# ME433-2021.net
KiCad netlist of a schematic drawn in EAGLE
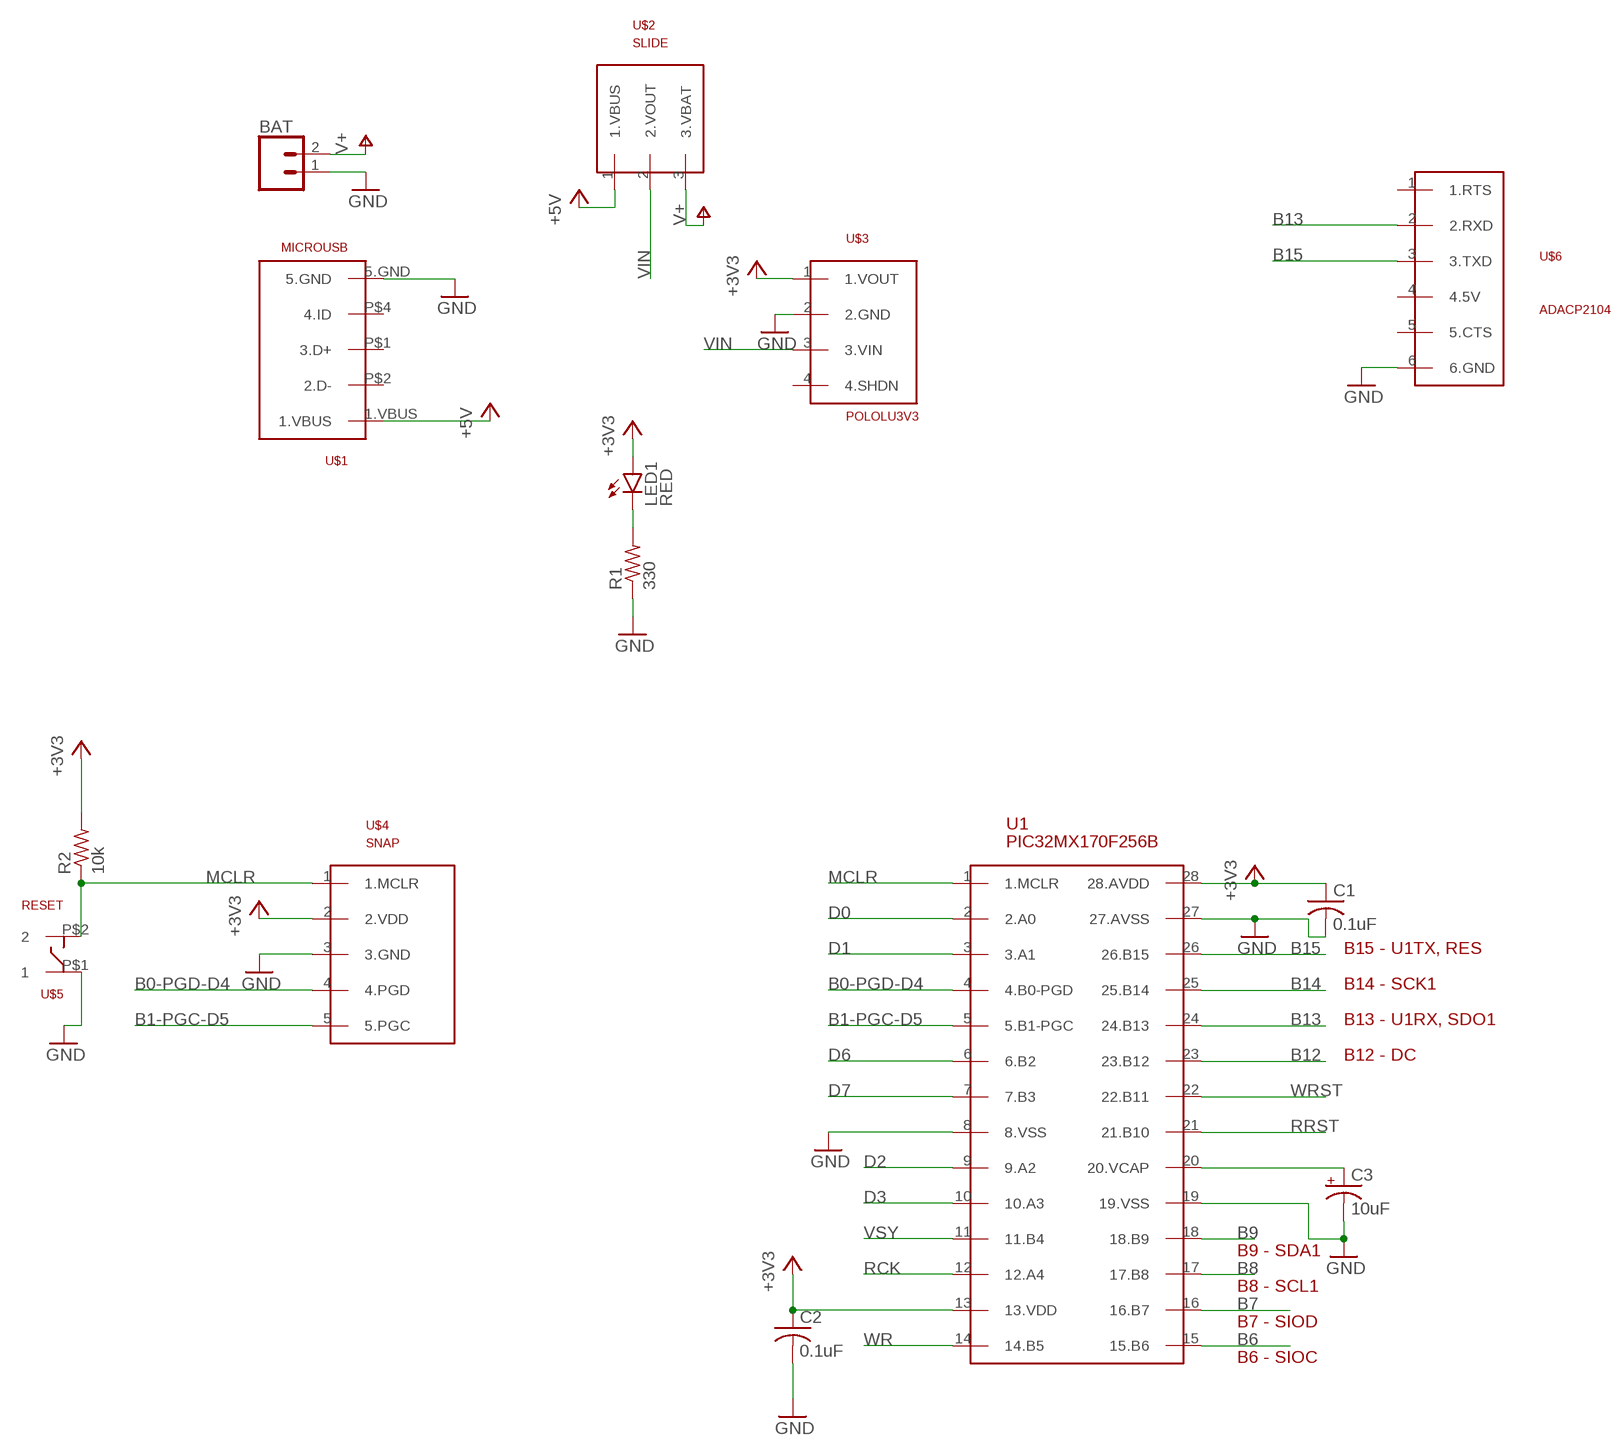
[diagram p0: schematic, sheet 1, part 1 of 2]
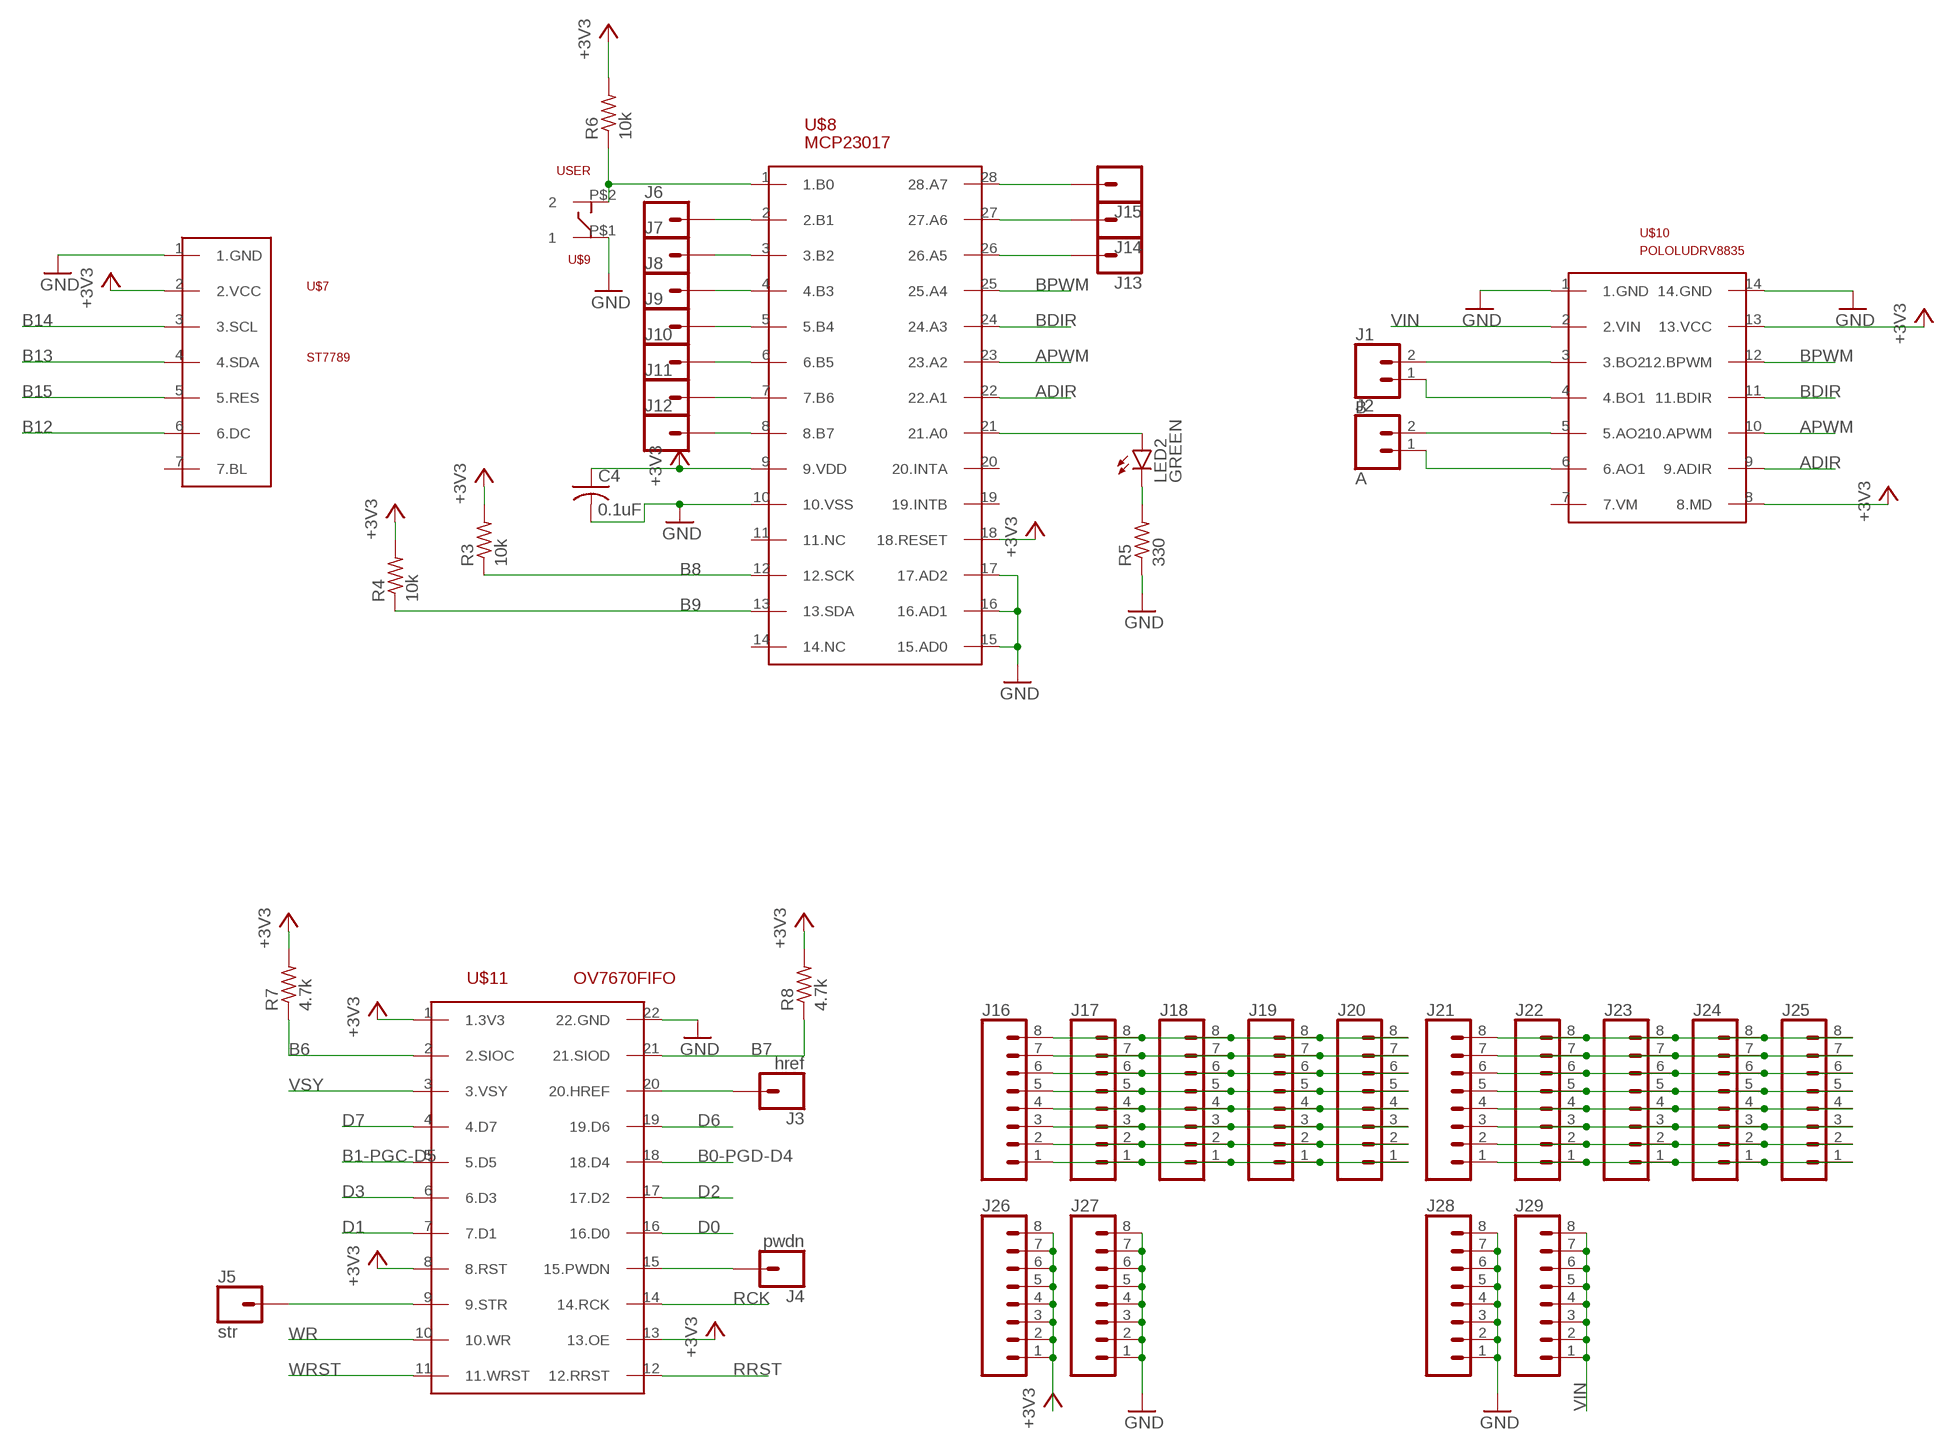
[diagram p1: schematic, sheet 1, part 2 of 2]

(export (version "E")
  (design (tool "Eeschema 10.0.6"))
  (components
    (comp (ref "BAT")
      (value "CONN_02")
      (footprint "eagle-import:1X02")
      (libsource (lib "eagle-import") (part "CONN_02"))
    )
    (comp (ref "C1")
      (value "0.1uF")
      (footprint "eagle-import:C025-030X050")
      (libsource (lib "eagle-import") (part "C-US025-030X050"))
    )
    (comp (ref "C2")
      (value "0.1uF")
      (footprint "eagle-import:C025-030X050")
      (libsource (lib "eagle-import") (part "C-US025-030X050"))
    )
    (comp (ref "C3")
      (value "10uF")
      (footprint "eagle-import:B45181B")
      (libsource (lib "eagle-import") (part "CPOL-USB45181B"))
    )
    (comp (ref "C4")
      (value "0.1uF")
      (footprint "eagle-import:C025-030X050")
      (libsource (lib "eagle-import") (part "C-US025-030X050"))
    )
    (comp (ref "J1")
      (value "B")
      (footprint "eagle-import:1X02")
      (libsource (lib "eagle-import") (part "CONN_02"))
    )
    (comp (ref "J2")
      (value "A")
      (footprint "eagle-import:1X02")
      (libsource (lib "eagle-import") (part "CONN_02"))
    )
    (comp (ref "J3")
      (value "href")
      (footprint "eagle-import:1X01")
      (libsource (lib "eagle-import") (part "CONN_01"))
    )
    (comp (ref "J4")
      (value "pwdn")
      (footprint "eagle-import:1X01")
      (libsource (lib "eagle-import") (part "CONN_01"))
    )
    (comp (ref "J5")
      (value "str")
      (footprint "eagle-import:1X01")
      (libsource (lib "eagle-import") (part "CONN_01"))
    )
    (comp (ref "J6")
      (value "CONN_01")
      (footprint "eagle-import:1X01")
      (libsource (lib "eagle-import") (part "CONN_01"))
    )
    (comp (ref "J7")
      (value "CONN_01")
      (footprint "eagle-import:1X01")
      (libsource (lib "eagle-import") (part "CONN_01"))
    )
    (comp (ref "J8")
      (value "CONN_01")
      (footprint "eagle-import:1X01")
      (libsource (lib "eagle-import") (part "CONN_01"))
    )
    (comp (ref "J9")
      (value "CONN_01")
      (footprint "eagle-import:1X01")
      (libsource (lib "eagle-import") (part "CONN_01"))
    )
    (comp (ref "J10")
      (value "CONN_01")
      (footprint "eagle-import:1X01")
      (libsource (lib "eagle-import") (part "CONN_01"))
    )
    (comp (ref "J11")
      (value "CONN_01")
      (footprint "eagle-import:1X01")
      (libsource (lib "eagle-import") (part "CONN_01"))
    )
    (comp (ref "J12")
      (value "CONN_01")
      (footprint "eagle-import:1X01")
      (libsource (lib "eagle-import") (part "CONN_01"))
    )
    (comp (ref "J13")
      (value "CONN_01")
      (footprint "eagle-import:1X01")
      (libsource (lib "eagle-import") (part "CONN_01"))
    )
    (comp (ref "J14")
      (value "CONN_01")
      (footprint "eagle-import:1X01")
      (libsource (lib "eagle-import") (part "CONN_01"))
    )
    (comp (ref "J15")
      (value "CONN_01")
      (footprint "eagle-import:1X01")
      (libsource (lib "eagle-import") (part "CONN_01"))
    )
    (comp (ref "J16")
      (value "CONN_08\"")
      (footprint "eagle-import:1X08")
      (libsource (lib "eagle-import") (part "CONN_08{dblquote}"))
    )
    (comp (ref "J17")
      (value "CONN_08\"")
      (footprint "eagle-import:1X08")
      (libsource (lib "eagle-import") (part "CONN_08{dblquote}"))
    )
    (comp (ref "J18")
      (value "CONN_08\"")
      (footprint "eagle-import:1X08")
      (libsource (lib "eagle-import") (part "CONN_08{dblquote}"))
    )
    (comp (ref "J19")
      (value "CONN_08\"")
      (footprint "eagle-import:1X08")
      (libsource (lib "eagle-import") (part "CONN_08{dblquote}"))
    )
    (comp (ref "J20")
      (value "CONN_08\"")
      (footprint "eagle-import:1X08")
      (libsource (lib "eagle-import") (part "CONN_08{dblquote}"))
    )
    (comp (ref "J21")
      (value "CONN_08\"")
      (footprint "eagle-import:1X08")
      (libsource (lib "eagle-import") (part "CONN_08{dblquote}"))
    )
    (comp (ref "J22")
      (value "CONN_08\"")
      (footprint "eagle-import:1X08")
      (libsource (lib "eagle-import") (part "CONN_08{dblquote}"))
    )
    (comp (ref "J23")
      (value "CONN_08\"")
      (footprint "eagle-import:1X08")
      (libsource (lib "eagle-import") (part "CONN_08{dblquote}"))
    )
    (comp (ref "J24")
      (value "CONN_08\"")
      (footprint "eagle-import:1X08")
      (libsource (lib "eagle-import") (part "CONN_08{dblquote}"))
    )
    (comp (ref "J25")
      (value "CONN_08\"")
      (footprint "eagle-import:1X08")
      (libsource (lib "eagle-import") (part "CONN_08{dblquote}"))
    )
    (comp (ref "J26")
      (value "CONN_08\"")
      (footprint "eagle-import:1X08")
      (libsource (lib "eagle-import") (part "CONN_08{dblquote}"))
    )
    (comp (ref "J27")
      (value "CONN_08\"")
      (footprint "eagle-import:1X08")
      (libsource (lib "eagle-import") (part "CONN_08{dblquote}"))
    )
    (comp (ref "J28")
      (value "CONN_08\"")
      (footprint "eagle-import:1X08")
      (libsource (lib "eagle-import") (part "CONN_08{dblquote}"))
    )
    (comp (ref "J29")
      (value "CONN_08\"")
      (footprint "eagle-import:1X08")
      (libsource (lib "eagle-import") (part "CONN_08{dblquote}"))
    )
    (comp (ref "LED1")
      (value "RED")
      (footprint "eagle-import:LED3MM")
      (libsource (lib "eagle-import") (part "LED3MM"))
    )
    (comp (ref "LED2")
      (value "GREEN")
      (footprint "eagle-import:LED3MM")
      (libsource (lib "eagle-import") (part "LED3MM"))
    )
    (comp (ref "R1")
      (value "330")
      (footprint "eagle-import:0207_10")
      (libsource (lib "eagle-import") (part "R-US_0207/10"))
    )
    (comp (ref "R2")
      (value "10k")
      (footprint "eagle-import:0207_10")
      (libsource (lib "eagle-import") (part "R-US_0207/10"))
    )
    (comp (ref "R3")
      (value "10k")
      (footprint "eagle-import:0207_10")
      (libsource (lib "eagle-import") (part "R-US_0207/10"))
    )
    (comp (ref "R4")
      (value "10k")
      (footprint "eagle-import:0207_10")
      (libsource (lib "eagle-import") (part "R-US_0207/10"))
    )
    (comp (ref "R5")
      (value "330")
      (footprint "eagle-import:0207_10")
      (libsource (lib "eagle-import") (part "R-US_0207/10"))
    )
    (comp (ref "R6")
      (value "10k")
      (footprint "eagle-import:0207_10")
      (libsource (lib "eagle-import") (part "R-US_0207/10"))
    )
    (comp (ref "R7")
      (value "4.7k")
      (footprint "eagle-import:0207_10")
      (libsource (lib "eagle-import") (part "R-US_0207/10"))
    )
    (comp (ref "R8")
      (value "4.7k")
      (footprint "eagle-import:0207_10")
      (libsource (lib "eagle-import") (part "R-US_0207/10"))
    )
    (comp (ref "U$1")
      (value "MICROUSB")
      (footprint "eagle-import:MICROUSB")
      (libsource (lib "eagle-import") (part "MICROUSB"))
    )
    (comp (ref "U$2")
      (value "SLIDE")
      (footprint "eagle-import:SLIDE")
      (libsource (lib "eagle-import") (part "SLIDE"))
    )
    (comp (ref "U$3")
      (value "POLOLU3V3")
      (footprint "eagle-import:POLOLU3V3")
      (libsource (lib "eagle-import") (part "POLOLU3V3"))
    )
    (comp (ref "U$4")
      (value "SNAP")
      (footprint "eagle-import:SNAP")
      (libsource (lib "eagle-import") (part "SNAP"))
    )
    (comp (ref "U$5")
      (value "RESET")
      (footprint "eagle-import:PUSH")
      (libsource (lib "eagle-import") (part "PUSH"))
    )
    (comp (ref "U$6")
      (value "ADACP2104")
      (footprint "eagle-import:ADACP2104")
      (libsource (lib "eagle-import") (part "ADACP2104"))
    )
    (comp (ref "U$7")
      (value "ST7789")
      (footprint "eagle-import:ST7789")
      (libsource (lib "eagle-import") (part "ST7789"))
    )
    (comp (ref "U$8")
      (value "MCP23017")
      (footprint "eagle-import:DIL28-3")
      (libsource (lib "eagle-import") (part "MCP23017"))
    )
    (comp (ref "U$9")
      (value "USER")
      (footprint "eagle-import:PUSH")
      (libsource (lib "eagle-import") (part "PUSH"))
    )
    (comp (ref "U$10")
      (value "POLOLUDRV8835")
      (footprint "eagle-import:POLOLUDRV8835")
      (libsource (lib "eagle-import") (part "POLOLUDRV8835"))
    )
    (comp (ref "U$11")
      (value "OV7670FIFO")
      (footprint "eagle-import:OV7670FIFO")
      (libsource (lib "eagle-import") (part "OV7670FIFO"))
    )
    (comp (ref "U1")
      (value "PIC32MX170F256B")
      (footprint "eagle-import:DIL28-3")
      (libsource (lib "eagle-import") (part "PIC32MX170F256B"))
    )
  )
  (nets
    (net (code "1") (name "+3V3") (class "Default")
      (node (ref "C1") (pin "1") (pinfunction "1_1") (pintype "passive"))
      (node (ref "C2") (pin "1") (pinfunction "1_1") (pintype "passive"))
      (node (ref "C4") (pin "1") (pinfunction "1_1") (pintype "passive"))
      (node (ref "J26") (pin "1") (pinfunction "1_1") (pintype "passive"))
      (node (ref "J26") (pin "2") (pinfunction "2_2") (pintype "passive"))
      (node (ref "J26") (pin "3") (pinfunction "3_3") (pintype "passive"))
      (node (ref "J26") (pin "4") (pinfunction "4_4") (pintype "passive"))
      (node (ref "J26") (pin "5") (pinfunction "5_5") (pintype "passive"))
      (node (ref "J26") (pin "6") (pinfunction "6_6") (pintype "passive"))
      (node (ref "J26") (pin "7") (pinfunction "7_7") (pintype "passive"))
      (node (ref "J26") (pin "8") (pinfunction "8_8") (pintype "passive"))
      (node (ref "LED1") (pin "A") (pinfunction "A_A") (pintype "passive"))
      (node (ref "R2") (pin "2") (pinfunction "2_2") (pintype "passive"))
      (node (ref "R3") (pin "2") (pinfunction "2_2") (pintype "passive"))
      (node (ref "R4") (pin "2") (pinfunction "2_2") (pintype "passive"))
      (node (ref "R6") (pin "2") (pinfunction "2_2") (pintype "passive"))
      (node (ref "R7") (pin "2") (pinfunction "2_2") (pintype "passive"))
      (node (ref "R8") (pin "2") (pinfunction "2_2") (pintype "passive"))
      (node (ref "U$10") (pin "13") (pinfunction "13.VCC_13") (pintype "bidirectional"))
      (node (ref "U$10") (pin "8") (pinfunction "8.MD_8") (pintype "bidirectional"))
      (node (ref "U$11") (pin "1") (pinfunction "1.3V3_1") (pintype "bidirectional"))
      (node (ref "U$11") (pin "13") (pinfunction "13.OE_13") (pintype "bidirectional"))
      (node (ref "U$11") (pin "8") (pinfunction "8.RST_8") (pintype "bidirectional"))
      (node (ref "U$3") (pin "1") (pinfunction "1.VOUT_1") (pintype "bidirectional"))
      (node (ref "U$4") (pin "2") (pinfunction "2.VDD_2") (pintype "bidirectional"))
      (node (ref "U$7") (pin "2") (pinfunction "2.VCC_2") (pintype "bidirectional"))
      (node (ref "U$8") (pin "18") (pinfunction "18.RESET_18") (pintype "bidirectional"))
      (node (ref "U$8") (pin "9") (pinfunction "9.VDD_9") (pintype "bidirectional"))
      (node (ref "U1") (pin "13") (pinfunction "13.VDD_13") (pintype "bidirectional"))
      (node (ref "U1") (pin "28") (pinfunction "28.AVDD_28") (pintype "bidirectional"))
    )
    (net (code "2") (name "+5V") (class "Default")
      (node (ref "U$1") (pin "1.VBUS") (pinfunction "1.VBUS_1.VBUS") (pintype "bidirectional"))
      (node (ref "U$2") (pin "1") (pinfunction "1.VBUS_1") (pintype "bidirectional"))
    )
    (net (code "3") (name "/ADIR") (class "Default")
      (node (ref "U$10") (pin "9") (pinfunction "9.ADIR_9") (pintype "bidirectional"))
      (node (ref "U$8") (pin "22") (pinfunction "22.A1_22") (pintype "bidirectional"))
    )
    (net (code "4") (name "/APWM") (class "Default")
      (node (ref "U$10") (pin "10") (pinfunction "10.APWM_10") (pintype "bidirectional"))
      (node (ref "U$8") (pin "23") (pinfunction "23.A2_23") (pintype "bidirectional"))
    )
    (net (code "5") (name "/B0-PGD-D4") (class "Default")
      (node (ref "U$11") (pin "18") (pinfunction "18.D4_18") (pintype "bidirectional"))
      (node (ref "U$4") (pin "4") (pinfunction "4.PGD_4") (pintype "bidirectional"))
      (node (ref "U1") (pin "4") (pinfunction "4.B0-PGD_4") (pintype "bidirectional"))
    )
    (net (code "6") (name "/B1-PGC-D5") (class "Default")
      (node (ref "U$11") (pin "5") (pinfunction "5.D5_5") (pintype "bidirectional"))
      (node (ref "U$4") (pin "5") (pinfunction "5.PGC_5") (pintype "bidirectional"))
      (node (ref "U1") (pin "5") (pinfunction "5.B1-PGC_5") (pintype "bidirectional"))
    )
    (net (code "7") (name "/B6") (class "Default")
      (node (ref "R7") (pin "1") (pinfunction "1_1") (pintype "passive"))
      (node (ref "U$11") (pin "2") (pinfunction "2.SIOC_2") (pintype "bidirectional"))
      (node (ref "U1") (pin "15") (pinfunction "15.B6_15") (pintype "bidirectional"))
    )
    (net (code "8") (name "/B7") (class "Default")
      (node (ref "R8") (pin "1") (pinfunction "1_1") (pintype "passive"))
      (node (ref "U$11") (pin "21") (pinfunction "21.SIOD_21") (pintype "bidirectional"))
      (node (ref "U1") (pin "16") (pinfunction "16.B7_16") (pintype "bidirectional"))
    )
    (net (code "9") (name "/B8") (class "Default")
      (node (ref "R3") (pin "1") (pinfunction "1_1") (pintype "passive"))
      (node (ref "U$8") (pin "12") (pinfunction "12.SCK_12") (pintype "bidirectional"))
      (node (ref "U1") (pin "17") (pinfunction "17.B8_17") (pintype "bidirectional"))
    )
    (net (code "10") (name "/B9") (class "Default")
      (node (ref "R4") (pin "1") (pinfunction "1_1") (pintype "passive"))
      (node (ref "U$8") (pin "13") (pinfunction "13.SDA_13") (pintype "bidirectional"))
      (node (ref "U1") (pin "18") (pinfunction "18.B9_18") (pintype "bidirectional"))
    )
    (net (code "11") (name "/B12") (class "Default")
      (node (ref "U$7") (pin "6") (pinfunction "6.DC_6") (pintype "bidirectional"))
      (node (ref "U1") (pin "23") (pinfunction "23.B12_23") (pintype "bidirectional"))
    )
    (net (code "12") (name "/B13") (class "Default")
      (node (ref "U$6") (pin "2") (pinfunction "2.RXD_2") (pintype "bidirectional"))
      (node (ref "U$7") (pin "4") (pinfunction "4.SDA_4") (pintype "bidirectional"))
      (node (ref "U1") (pin "24") (pinfunction "24.B13_24") (pintype "bidirectional"))
    )
    (net (code "13") (name "/B14") (class "Default")
      (node (ref "U$7") (pin "3") (pinfunction "3.SCL_3") (pintype "bidirectional"))
      (node (ref "U1") (pin "25") (pinfunction "25.B14_25") (pintype "bidirectional"))
    )
    (net (code "14") (name "/B15") (class "Default")
      (node (ref "U$6") (pin "3") (pinfunction "3.TXD_3") (pintype "bidirectional"))
      (node (ref "U$7") (pin "5") (pinfunction "5.RES_5") (pintype "bidirectional"))
      (node (ref "U1") (pin "26") (pinfunction "26.B15_26") (pintype "bidirectional"))
    )
    (net (code "15") (name "/BDIR") (class "Default")
      (node (ref "U$10") (pin "11") (pinfunction "11.BDIR_11") (pintype "bidirectional"))
      (node (ref "U$8") (pin "24") (pinfunction "24.A3_24") (pintype "bidirectional"))
    )
    (net (code "16") (name "/BPWM") (class "Default")
      (node (ref "U$10") (pin "12") (pinfunction "12.BPWM_12") (pintype "bidirectional"))
      (node (ref "U$8") (pin "25") (pinfunction "25.A4_25") (pintype "bidirectional"))
    )
    (net (code "17") (name "/D0") (class "Default")
      (node (ref "U$11") (pin "16") (pinfunction "16.D0_16") (pintype "bidirectional"))
      (node (ref "U1") (pin "2") (pinfunction "2.A0_2") (pintype "bidirectional"))
    )
    (net (code "18") (name "/D1") (class "Default")
      (node (ref "U$11") (pin "7") (pinfunction "7.D1_7") (pintype "bidirectional"))
      (node (ref "U1") (pin "3") (pinfunction "3.A1_3") (pintype "bidirectional"))
    )
    (net (code "19") (name "/D2") (class "Default")
      (node (ref "U$11") (pin "17") (pinfunction "17.D2_17") (pintype "bidirectional"))
      (node (ref "U1") (pin "9") (pinfunction "9.A2_9") (pintype "bidirectional"))
    )
    (net (code "20") (name "/D3") (class "Default")
      (node (ref "U$11") (pin "6") (pinfunction "6.D3_6") (pintype "bidirectional"))
      (node (ref "U1") (pin "10") (pinfunction "10.A3_10") (pintype "bidirectional"))
    )
    (net (code "21") (name "/D6") (class "Default")
      (node (ref "U$11") (pin "19") (pinfunction "19.D6_19") (pintype "bidirectional"))
      (node (ref "U1") (pin "6") (pinfunction "6.B2_6") (pintype "bidirectional"))
    )
    (net (code "22") (name "/D7") (class "Default")
      (node (ref "U$11") (pin "4") (pinfunction "4.D7_4") (pintype "bidirectional"))
      (node (ref "U1") (pin "7") (pinfunction "7.B3_7") (pintype "bidirectional"))
    )
    (net (code "23") (name "/MCLR") (class "Default")
      (node (ref "R2") (pin "1") (pinfunction "1_1") (pintype "passive"))
      (node (ref "U$4") (pin "1") (pinfunction "1.MCLR_1") (pintype "bidirectional"))
      (node (ref "U$5") (pin "P$2") (pinfunction "2_P$2") (pintype "bidirectional"))
      (node (ref "U1") (pin "1") (pinfunction "1.MCLR_1") (pintype "bidirectional"))
    )
    (net (code "24") (name "/RCK") (class "Default")
      (node (ref "U$11") (pin "14") (pinfunction "14.RCK_14") (pintype "bidirectional"))
      (node (ref "U1") (pin "12") (pinfunction "12.A4_12") (pintype "bidirectional"))
    )
    (net (code "25") (name "/RRST") (class "Default")
      (node (ref "U$11") (pin "12") (pinfunction "12.RRST_12") (pintype "bidirectional"))
      (node (ref "U1") (pin "21") (pinfunction "21.B10_21") (pintype "bidirectional"))
    )
    (net (code "26") (name "/VIN") (class "Default")
      (node (ref "J29") (pin "1") (pinfunction "1_1") (pintype "passive"))
      (node (ref "J29") (pin "2") (pinfunction "2_2") (pintype "passive"))
      (node (ref "J29") (pin "3") (pinfunction "3_3") (pintype "passive"))
      (node (ref "J29") (pin "4") (pinfunction "4_4") (pintype "passive"))
      (node (ref "J29") (pin "5") (pinfunction "5_5") (pintype "passive"))
      (node (ref "J29") (pin "6") (pinfunction "6_6") (pintype "passive"))
      (node (ref "J29") (pin "7") (pinfunction "7_7") (pintype "passive"))
      (node (ref "J29") (pin "8") (pinfunction "8_8") (pintype "passive"))
      (node (ref "U$10") (pin "2") (pinfunction "2.VIN_2") (pintype "bidirectional"))
      (node (ref "U$2") (pin "2") (pinfunction "2.VOUT_2") (pintype "bidirectional"))
      (node (ref "U$3") (pin "3") (pinfunction "3.VIN_3") (pintype "bidirectional"))
    )
    (net (code "27") (name "/VSY") (class "Default")
      (node (ref "U$11") (pin "3") (pinfunction "3.VSY_3") (pintype "bidirectional"))
      (node (ref "U1") (pin "11") (pinfunction "11.B4_11") (pintype "bidirectional"))
    )
    (net (code "28") (name "/WR") (class "Default")
      (node (ref "U$11") (pin "10") (pinfunction "10.WR_10") (pintype "bidirectional"))
      (node (ref "U1") (pin "14") (pinfunction "14.B5_14") (pintype "bidirectional"))
    )
    (net (code "29") (name "/WRST") (class "Default")
      (node (ref "U$11") (pin "11") (pinfunction "11.WRST_11") (pintype "bidirectional"))
      (node (ref "U1") (pin "22") (pinfunction "22.B11_22") (pintype "bidirectional"))
    )
    (net (code "30") (name "GND") (class "Default")
      (node (ref "BAT") (pin "1") (pinfunction "1_1") (pintype "passive"))
      (node (ref "C1") (pin "2") (pinfunction "2_2") (pintype "passive"))
      (node (ref "C2") (pin "2") (pinfunction "2_2") (pintype "passive"))
      (node (ref "C3") (pin "-") (pinfunction "-_-") (pintype "passive"))
      (node (ref "C4") (pin "2") (pinfunction "2_2") (pintype "passive"))
      (node (ref "J27") (pin "1") (pinfunction "1_1") (pintype "passive"))
      (node (ref "J27") (pin "2") (pinfunction "2_2") (pintype "passive"))
      (node (ref "J27") (pin "3") (pinfunction "3_3") (pintype "passive"))
      (node (ref "J27") (pin "4") (pinfunction "4_4") (pintype "passive"))
      (node (ref "J27") (pin "5") (pinfunction "5_5") (pintype "passive"))
      (node (ref "J27") (pin "6") (pinfunction "6_6") (pintype "passive"))
      (node (ref "J27") (pin "7") (pinfunction "7_7") (pintype "passive"))
      (node (ref "J27") (pin "8") (pinfunction "8_8") (pintype "passive"))
      (node (ref "J28") (pin "1") (pinfunction "1_1") (pintype "passive"))
      (node (ref "J28") (pin "2") (pinfunction "2_2") (pintype "passive"))
      (node (ref "J28") (pin "3") (pinfunction "3_3") (pintype "passive"))
      (node (ref "J28") (pin "4") (pinfunction "4_4") (pintype "passive"))
      (node (ref "J28") (pin "5") (pinfunction "5_5") (pintype "passive"))
      (node (ref "J28") (pin "6") (pinfunction "6_6") (pintype "passive"))
      (node (ref "J28") (pin "7") (pinfunction "7_7") (pintype "passive"))
      (node (ref "J28") (pin "8") (pinfunction "8_8") (pintype "passive"))
      (node (ref "R1") (pin "1") (pinfunction "1_1") (pintype "passive"))
      (node (ref "R5") (pin "1") (pinfunction "1_1") (pintype "passive"))
      (node (ref "U$1") (pin "5.GND") (pinfunction "5.GND_5.GND") (pintype "bidirectional"))
      (node (ref "U$10") (pin "1") (pinfunction "1.GND_1") (pintype "bidirectional"))
      (node (ref "U$10") (pin "14") (pinfunction "14.GND_14") (pintype "bidirectional"))
      (node (ref "U$11") (pin "22") (pinfunction "22.GND_22") (pintype "bidirectional"))
      (node (ref "U$3") (pin "2") (pinfunction "2.GND_2") (pintype "bidirectional"))
      (node (ref "U$4") (pin "3") (pinfunction "3.GND_3") (pintype "bidirectional"))
      (node (ref "U$5") (pin "P$1") (pinfunction "1_P$1") (pintype "bidirectional"))
      (node (ref "U$6") (pin "6") (pinfunction "6.GND_6") (pintype "bidirectional"))
      (node (ref "U$7") (pin "1") (pinfunction "1.GND_1") (pintype "bidirectional"))
      (node (ref "U$8") (pin "10") (pinfunction "10.VSS_10") (pintype "bidirectional"))
      (node (ref "U$8") (pin "15") (pinfunction "15.AD0_15") (pintype "bidirectional"))
      (node (ref "U$8") (pin "16") (pinfunction "16.AD1_16") (pintype "bidirectional"))
      (node (ref "U$8") (pin "17") (pinfunction "17.AD2_17") (pintype "bidirectional"))
      (node (ref "U$9") (pin "P$1") (pinfunction "1_P$1") (pintype "bidirectional"))
      (node (ref "U1") (pin "19") (pinfunction "19.VSS_19") (pintype "bidirectional"))
      (node (ref "U1") (pin "27") (pinfunction "27.AVSS_27") (pintype "bidirectional"))
      (node (ref "U1") (pin "8") (pinfunction "8.VSS_8") (pintype "bidirectional"))
    )
    (net (code "31") (name "Net-(J16-Pad1)") (class "Default")
      (node (ref "J16") (pin "1") (pinfunction "1_1") (pintype "passive"))
      (node (ref "J17") (pin "1") (pinfunction "1_1") (pintype "passive"))
      (node (ref "J18") (pin "1") (pinfunction "1_1") (pintype "passive"))
      (node (ref "J19") (pin "1") (pinfunction "1_1") (pintype "passive"))
      (node (ref "J20") (pin "1") (pinfunction "1_1") (pintype "passive"))
    )
    (net (code "32") (name "Net-(J16-Pad2)") (class "Default")
      (node (ref "J16") (pin "2") (pinfunction "2_2") (pintype "passive"))
      (node (ref "J17") (pin "2") (pinfunction "2_2") (pintype "passive"))
      (node (ref "J18") (pin "2") (pinfunction "2_2") (pintype "passive"))
      (node (ref "J19") (pin "2") (pinfunction "2_2") (pintype "passive"))
      (node (ref "J20") (pin "2") (pinfunction "2_2") (pintype "passive"))
    )
    (net (code "33") (name "Net-(J16-Pad3)") (class "Default")
      (node (ref "J16") (pin "3") (pinfunction "3_3") (pintype "passive"))
      (node (ref "J17") (pin "3") (pinfunction "3_3") (pintype "passive"))
      (node (ref "J18") (pin "3") (pinfunction "3_3") (pintype "passive"))
      (node (ref "J19") (pin "3") (pinfunction "3_3") (pintype "passive"))
      (node (ref "J20") (pin "3") (pinfunction "3_3") (pintype "passive"))
    )
    (net (code "34") (name "Net-(J16-Pad4)") (class "Default")
      (node (ref "J16") (pin "4") (pinfunction "4_4") (pintype "passive"))
      (node (ref "J17") (pin "4") (pinfunction "4_4") (pintype "passive"))
      (node (ref "J18") (pin "4") (pinfunction "4_4") (pintype "passive"))
      (node (ref "J19") (pin "4") (pinfunction "4_4") (pintype "passive"))
      (node (ref "J20") (pin "4") (pinfunction "4_4") (pintype "passive"))
    )
    (net (code "35") (name "Net-(J16-Pad5)") (class "Default")
      (node (ref "J16") (pin "5") (pinfunction "5_5") (pintype "passive"))
      (node (ref "J17") (pin "5") (pinfunction "5_5") (pintype "passive"))
      (node (ref "J18") (pin "5") (pinfunction "5_5") (pintype "passive"))
      (node (ref "J19") (pin "5") (pinfunction "5_5") (pintype "passive"))
      (node (ref "J20") (pin "5") (pinfunction "5_5") (pintype "passive"))
    )
    (net (code "36") (name "Net-(J16-Pad6)") (class "Default")
      (node (ref "J16") (pin "6") (pinfunction "6_6") (pintype "passive"))
      (node (ref "J17") (pin "6") (pinfunction "6_6") (pintype "passive"))
      (node (ref "J18") (pin "6") (pinfunction "6_6") (pintype "passive"))
      (node (ref "J19") (pin "6") (pinfunction "6_6") (pintype "passive"))
      (node (ref "J20") (pin "6") (pinfunction "6_6") (pintype "passive"))
    )
    (net (code "37") (name "Net-(J16-Pad7)") (class "Default")
      (node (ref "J16") (pin "7") (pinfunction "7_7") (pintype "passive"))
      (node (ref "J17") (pin "7") (pinfunction "7_7") (pintype "passive"))
      (node (ref "J18") (pin "7") (pinfunction "7_7") (pintype "passive"))
      (node (ref "J19") (pin "7") (pinfunction "7_7") (pintype "passive"))
      (node (ref "J20") (pin "7") (pinfunction "7_7") (pintype "passive"))
    )
    (net (code "38") (name "Net-(J16-Pad8)") (class "Default")
      (node (ref "J16") (pin "8") (pinfunction "8_8") (pintype "passive"))
      (node (ref "J17") (pin "8") (pinfunction "8_8") (pintype "passive"))
      (node (ref "J18") (pin "8") (pinfunction "8_8") (pintype "passive"))
      (node (ref "J19") (pin "8") (pinfunction "8_8") (pintype "passive"))
      (node (ref "J20") (pin "8") (pinfunction "8_8") (pintype "passive"))
    )
    (net (code "39") (name "Net-(J21-Pad1)") (class "Default")
      (node (ref "J21") (pin "1") (pinfunction "1_1") (pintype "passive"))
      (node (ref "J22") (pin "1") (pinfunction "1_1") (pintype "passive"))
      (node (ref "J23") (pin "1") (pinfunction "1_1") (pintype "passive"))
      (node (ref "J24") (pin "1") (pinfunction "1_1") (pintype "passive"))
      (node (ref "J25") (pin "1") (pinfunction "1_1") (pintype "passive"))
    )
    (net (code "40") (name "Net-(J21-Pad2)") (class "Default")
      (node (ref "J21") (pin "2") (pinfunction "2_2") (pintype "passive"))
      (node (ref "J22") (pin "2") (pinfunction "2_2") (pintype "passive"))
      (node (ref "J23") (pin "2") (pinfunction "2_2") (pintype "passive"))
      (node (ref "J24") (pin "2") (pinfunction "2_2") (pintype "passive"))
      (node (ref "J25") (pin "2") (pinfunction "2_2") (pintype "passive"))
    )
    (net (code "41") (name "Net-(J21-Pad3)") (class "Default")
      (node (ref "J21") (pin "3") (pinfunction "3_3") (pintype "passive"))
      (node (ref "J22") (pin "3") (pinfunction "3_3") (pintype "passive"))
      (node (ref "J23") (pin "3") (pinfunction "3_3") (pintype "passive"))
      (node (ref "J24") (pin "3") (pinfunction "3_3") (pintype "passive"))
      (node (ref "J25") (pin "3") (pinfunction "3_3") (pintype "passive"))
    )
    (net (code "42") (name "Net-(J21-Pad4)") (class "Default")
      (node (ref "J21") (pin "4") (pinfunction "4_4") (pintype "passive"))
      (node (ref "J22") (pin "4") (pinfunction "4_4") (pintype "passive"))
      (node (ref "J23") (pin "4") (pinfunction "4_4") (pintype "passive"))
      (node (ref "J24") (pin "4") (pinfunction "4_4") (pintype "passive"))
      (node (ref "J25") (pin "4") (pinfunction "4_4") (pintype "passive"))
    )
    (net (code "43") (name "Net-(J21-Pad5)") (class "Default")
      (node (ref "J21") (pin "5") (pinfunction "5_5") (pintype "passive"))
      (node (ref "J22") (pin "5") (pinfunction "5_5") (pintype "passive"))
      (node (ref "J23") (pin "5") (pinfunction "5_5") (pintype "passive"))
      (node (ref "J24") (pin "5") (pinfunction "5_5") (pintype "passive"))
      (node (ref "J25") (pin "5") (pinfunction "5_5") (pintype "passive"))
    )
    (net (code "44") (name "Net-(J21-Pad6)") (class "Default")
      (node (ref "J21") (pin "6") (pinfunction "6_6") (pintype "passive"))
      (node (ref "J22") (pin "6") (pinfunction "6_6") (pintype "passive"))
      (node (ref "J23") (pin "6") (pinfunction "6_6") (pintype "passive"))
      (node (ref "J24") (pin "6") (pinfunction "6_6") (pintype "passive"))
      (node (ref "J25") (pin "6") (pinfunction "6_6") (pintype "passive"))
    )
    (net (code "45") (name "Net-(J21-Pad7)") (class "Default")
      (node (ref "J21") (pin "7") (pinfunction "7_7") (pintype "passive"))
      (node (ref "J22") (pin "7") (pinfunction "7_7") (pintype "passive"))
      (node (ref "J23") (pin "7") (pinfunction "7_7") (pintype "passive"))
      (node (ref "J24") (pin "7") (pinfunction "7_7") (pintype "passive"))
      (node (ref "J25") (pin "7") (pinfunction "7_7") (pintype "passive"))
    )
    (net (code "46") (name "Net-(J21-Pad8)") (class "Default")
      (node (ref "J21") (pin "8") (pinfunction "8_8") (pintype "passive"))
      (node (ref "J22") (pin "8") (pinfunction "8_8") (pintype "passive"))
      (node (ref "J23") (pin "8") (pinfunction "8_8") (pintype "passive"))
      (node (ref "J24") (pin "8") (pinfunction "8_8") (pintype "passive"))
      (node (ref "J25") (pin "8") (pinfunction "8_8") (pintype "passive"))
    )
    (net (code "47") (name "Net-(LED1-C)") (class "Default")
      (node (ref "LED1") (pin "K") (pinfunction "C_K") (pintype "passive"))
      (node (ref "R1") (pin "2") (pinfunction "2_2") (pintype "passive"))
    )
    (net (code "48") (name "Net-(LED2-C)") (class "Default")
      (node (ref "LED2") (pin "K") (pinfunction "C_K") (pintype "passive"))
      (node (ref "R5") (pin "2") (pinfunction "2_2") (pintype "passive"))
    )
    (net (code "49") (name "Net-(U$8-1.B0)") (class "Default")
      (node (ref "R6") (pin "1") (pinfunction "1_1") (pintype "passive"))
      (node (ref "U$8") (pin "1") (pinfunction "1.B0_1") (pintype "bidirectional"))
      (node (ref "U$9") (pin "P$2") (pinfunction "2_P$2") (pintype "bidirectional"))
    )
    (net (code "50") (name "Net-(U$8-2.B1)") (class "Default")
      (node (ref "J6") (pin "1") (pinfunction "1_1") (pintype "passive"))
      (node (ref "U$8") (pin "2") (pinfunction "2.B1_2") (pintype "bidirectional"))
    )
    (net (code "51") (name "Net-(U$8-3.B2)") (class "Default")
      (node (ref "J7") (pin "1") (pinfunction "1_1") (pintype "passive"))
      (node (ref "U$8") (pin "3") (pinfunction "3.B2_3") (pintype "bidirectional"))
    )
    (net (code "52") (name "Net-(U$8-4.B3)") (class "Default")
      (node (ref "J8") (pin "1") (pinfunction "1_1") (pintype "passive"))
      (node (ref "U$8") (pin "4") (pinfunction "4.B3_4") (pintype "bidirectional"))
    )
    (net (code "53") (name "Net-(U$8-5.B4)") (class "Default")
      (node (ref "J9") (pin "1") (pinfunction "1_1") (pintype "passive"))
      (node (ref "U$8") (pin "5") (pinfunction "5.B4_5") (pintype "bidirectional"))
    )
    (net (code "54") (name "Net-(U$8-6.B5)") (class "Default")
      (node (ref "J10") (pin "1") (pinfunction "1_1") (pintype "passive"))
      (node (ref "U$8") (pin "6") (pinfunction "6.B5_6") (pintype "bidirectional"))
    )
    (net (code "55") (name "Net-(U$8-7.B6)") (class "Default")
      (node (ref "J11") (pin "1") (pinfunction "1_1") (pintype "passive"))
      (node (ref "U$8") (pin "7") (pinfunction "7.B6_7") (pintype "bidirectional"))
    )
    (net (code "56") (name "Net-(U$8-8.B7)") (class "Default")
      (node (ref "J12") (pin "1") (pinfunction "1_1") (pintype "passive"))
      (node (ref "U$8") (pin "8") (pinfunction "8.B7_8") (pintype "bidirectional"))
    )
    (net (code "57") (name "Net-(U$8-21.A0)") (class "Default")
      (node (ref "LED2") (pin "A") (pinfunction "A_A") (pintype "passive"))
      (node (ref "U$8") (pin "21") (pinfunction "21.A0_21") (pintype "bidirectional"))
    )
    (net (code "58") (name "Net-(U$8-26.A5)") (class "Default")
      (node (ref "J13") (pin "1") (pinfunction "1_1") (pintype "passive"))
      (node (ref "U$8") (pin "26") (pinfunction "26.A5_26") (pintype "bidirectional"))
    )
    (net (code "59") (name "Net-(U$8-27.A6)") (class "Default")
      (node (ref "J14") (pin "1") (pinfunction "1_1") (pintype "passive"))
      (node (ref "U$8") (pin "27") (pinfunction "27.A6_27") (pintype "bidirectional"))
    )
    (net (code "60") (name "Net-(U$8-28.A7)") (class "Default")
      (node (ref "J15") (pin "1") (pinfunction "1_1") (pintype "passive"))
      (node (ref "U$8") (pin "28") (pinfunction "28.A7_28") (pintype "bidirectional"))
    )
    (net (code "61") (name "Net-(U$10-3.BO2)") (class "Default")
      (node (ref "J1") (pin "2") (pinfunction "2_2") (pintype "passive"))
      (node (ref "U$10") (pin "3") (pinfunction "3.BO2_3") (pintype "bidirectional"))
    )
    (net (code "62") (name "Net-(U$10-4.BO1)") (class "Default")
      (node (ref "J1") (pin "1") (pinfunction "1_1") (pintype "passive"))
      (node (ref "U$10") (pin "4") (pinfunction "4.BO1_4") (pintype "bidirectional"))
    )
    (net (code "63") (name "Net-(U$10-5.AO2)") (class "Default")
      (node (ref "J2") (pin "2") (pinfunction "2_2") (pintype "passive"))
      (node (ref "U$10") (pin "5") (pinfunction "5.AO2_5") (pintype "bidirectional"))
    )
    (net (code "64") (name "Net-(U$10-6.AO1)") (class "Default")
      (node (ref "J2") (pin "1") (pinfunction "1_1") (pintype "passive"))
      (node (ref "U$10") (pin "6") (pinfunction "6.AO1_6") (pintype "bidirectional"))
    )
    (net (code "65") (name "Net-(U$11-9.STR)") (class "Default")
      (node (ref "J5") (pin "1") (pinfunction "1_1") (pintype "passive"))
      (node (ref "U$11") (pin "9") (pinfunction "9.STR_9") (pintype "bidirectional"))
    )
    (net (code "66") (name "Net-(U$11-15.PWDN)") (class "Default")
      (node (ref "J4") (pin "1") (pinfunction "1_1") (pintype "passive"))
      (node (ref "U$11") (pin "15") (pinfunction "15.PWDN_15") (pintype "bidirectional"))
    )
    (net (code "67") (name "Net-(U$11-20.HREF)") (class "Default")
      (node (ref "J3") (pin "1") (pinfunction "1_1") (pintype "passive"))
      (node (ref "U$11") (pin "20") (pinfunction "20.HREF_20") (pintype "bidirectional"))
    )
    (net (code "68") (name "Net-(U1-20.VCAP)") (class "Default")
      (node (ref "C3") (pin "+") (pinfunction "+_+") (pintype "passive"))
      (node (ref "U1") (pin "20") (pinfunction "20.VCAP_20") (pintype "bidirectional"))
    )
    (net (code "69") (name "V+") (class "Default")
      (node (ref "BAT") (pin "2") (pinfunction "2_2") (pintype "passive"))
      (node (ref "U$2") (pin "3") (pinfunction "3.VBAT_3") (pintype "bidirectional"))
    )
    (net (code "70") (name "unconnected-(U$1-2.D--PadP$2)") (class "Default")
      (node (ref "U$1") (pin "P$2") (pinfunction "2.D-_P$2") (pintype "bidirectional"))
    )
    (net (code "71") (name "unconnected-(U$1-3.D+-PadP$1)") (class "Default")
      (node (ref "U$1") (pin "P$1") (pinfunction "3.D+_P$1") (pintype "bidirectional"))
    )
    (net (code "72") (name "unconnected-(U$1-4.ID-PadP$4)") (class "Default")
      (node (ref "U$1") (pin "P$4") (pinfunction "4.ID_P$4") (pintype "bidirectional"))
    )
    (net (code "73") (name "unconnected-(U$3-4.SHDN-Pad4)") (class "Default")
      (node (ref "U$3") (pin "4") (pinfunction "4.SHDN_4") (pintype "bidirectional"))
    )
    (net (code "74") (name "unconnected-(U$6-1.RTS-Pad1)") (class "Default")
      (node (ref "U$6") (pin "1") (pinfunction "1.RTS_1") (pintype "bidirectional"))
    )
    (net (code "75") (name "unconnected-(U$6-4.5V-Pad4)") (class "Default")
      (node (ref "U$6") (pin "4") (pinfunction "4.5V_4") (pintype "bidirectional"))
    )
    (net (code "76") (name "unconnected-(U$6-5.CTS-Pad5)") (class "Default")
      (node (ref "U$6") (pin "5") (pinfunction "5.CTS_5") (pintype "bidirectional"))
    )
    (net (code "77") (name "unconnected-(U$7-7.BL-Pad7)") (class "Default")
      (node (ref "U$7") (pin "7") (pinfunction "7.BL_7") (pintype "bidirectional"))
    )
    (net (code "78") (name "unconnected-(U$8-11.NC-Pad11)") (class "Default")
      (node (ref "U$8") (pin "11") (pinfunction "11.NC_11") (pintype "bidirectional"))
    )
    (net (code "79") (name "unconnected-(U$8-14.NC-Pad14)") (class "Default")
      (node (ref "U$8") (pin "14") (pinfunction "14.NC_14") (pintype "bidirectional"))
    )
    (net (code "80") (name "unconnected-(U$8-19.INTB-Pad19)") (class "Default")
      (node (ref "U$8") (pin "19") (pinfunction "19.INTB_19") (pintype "bidirectional"))
    )
    (net (code "81") (name "unconnected-(U$8-20.INTA-Pad20)") (class "Default")
      (node (ref "U$8") (pin "20") (pinfunction "20.INTA_20") (pintype "bidirectional"))
    )
    (net (code "82") (name "unconnected-(U$10-7.VM-Pad7)") (class "Default")
      (node (ref "U$10") (pin "7") (pinfunction "7.VM_7") (pintype "bidirectional"))
    )
  )
)
